# EVB-ANNA-B5_SCHEM_0007_mikroE.net
KiCad netlist of a schematic drawn in Altium Designer
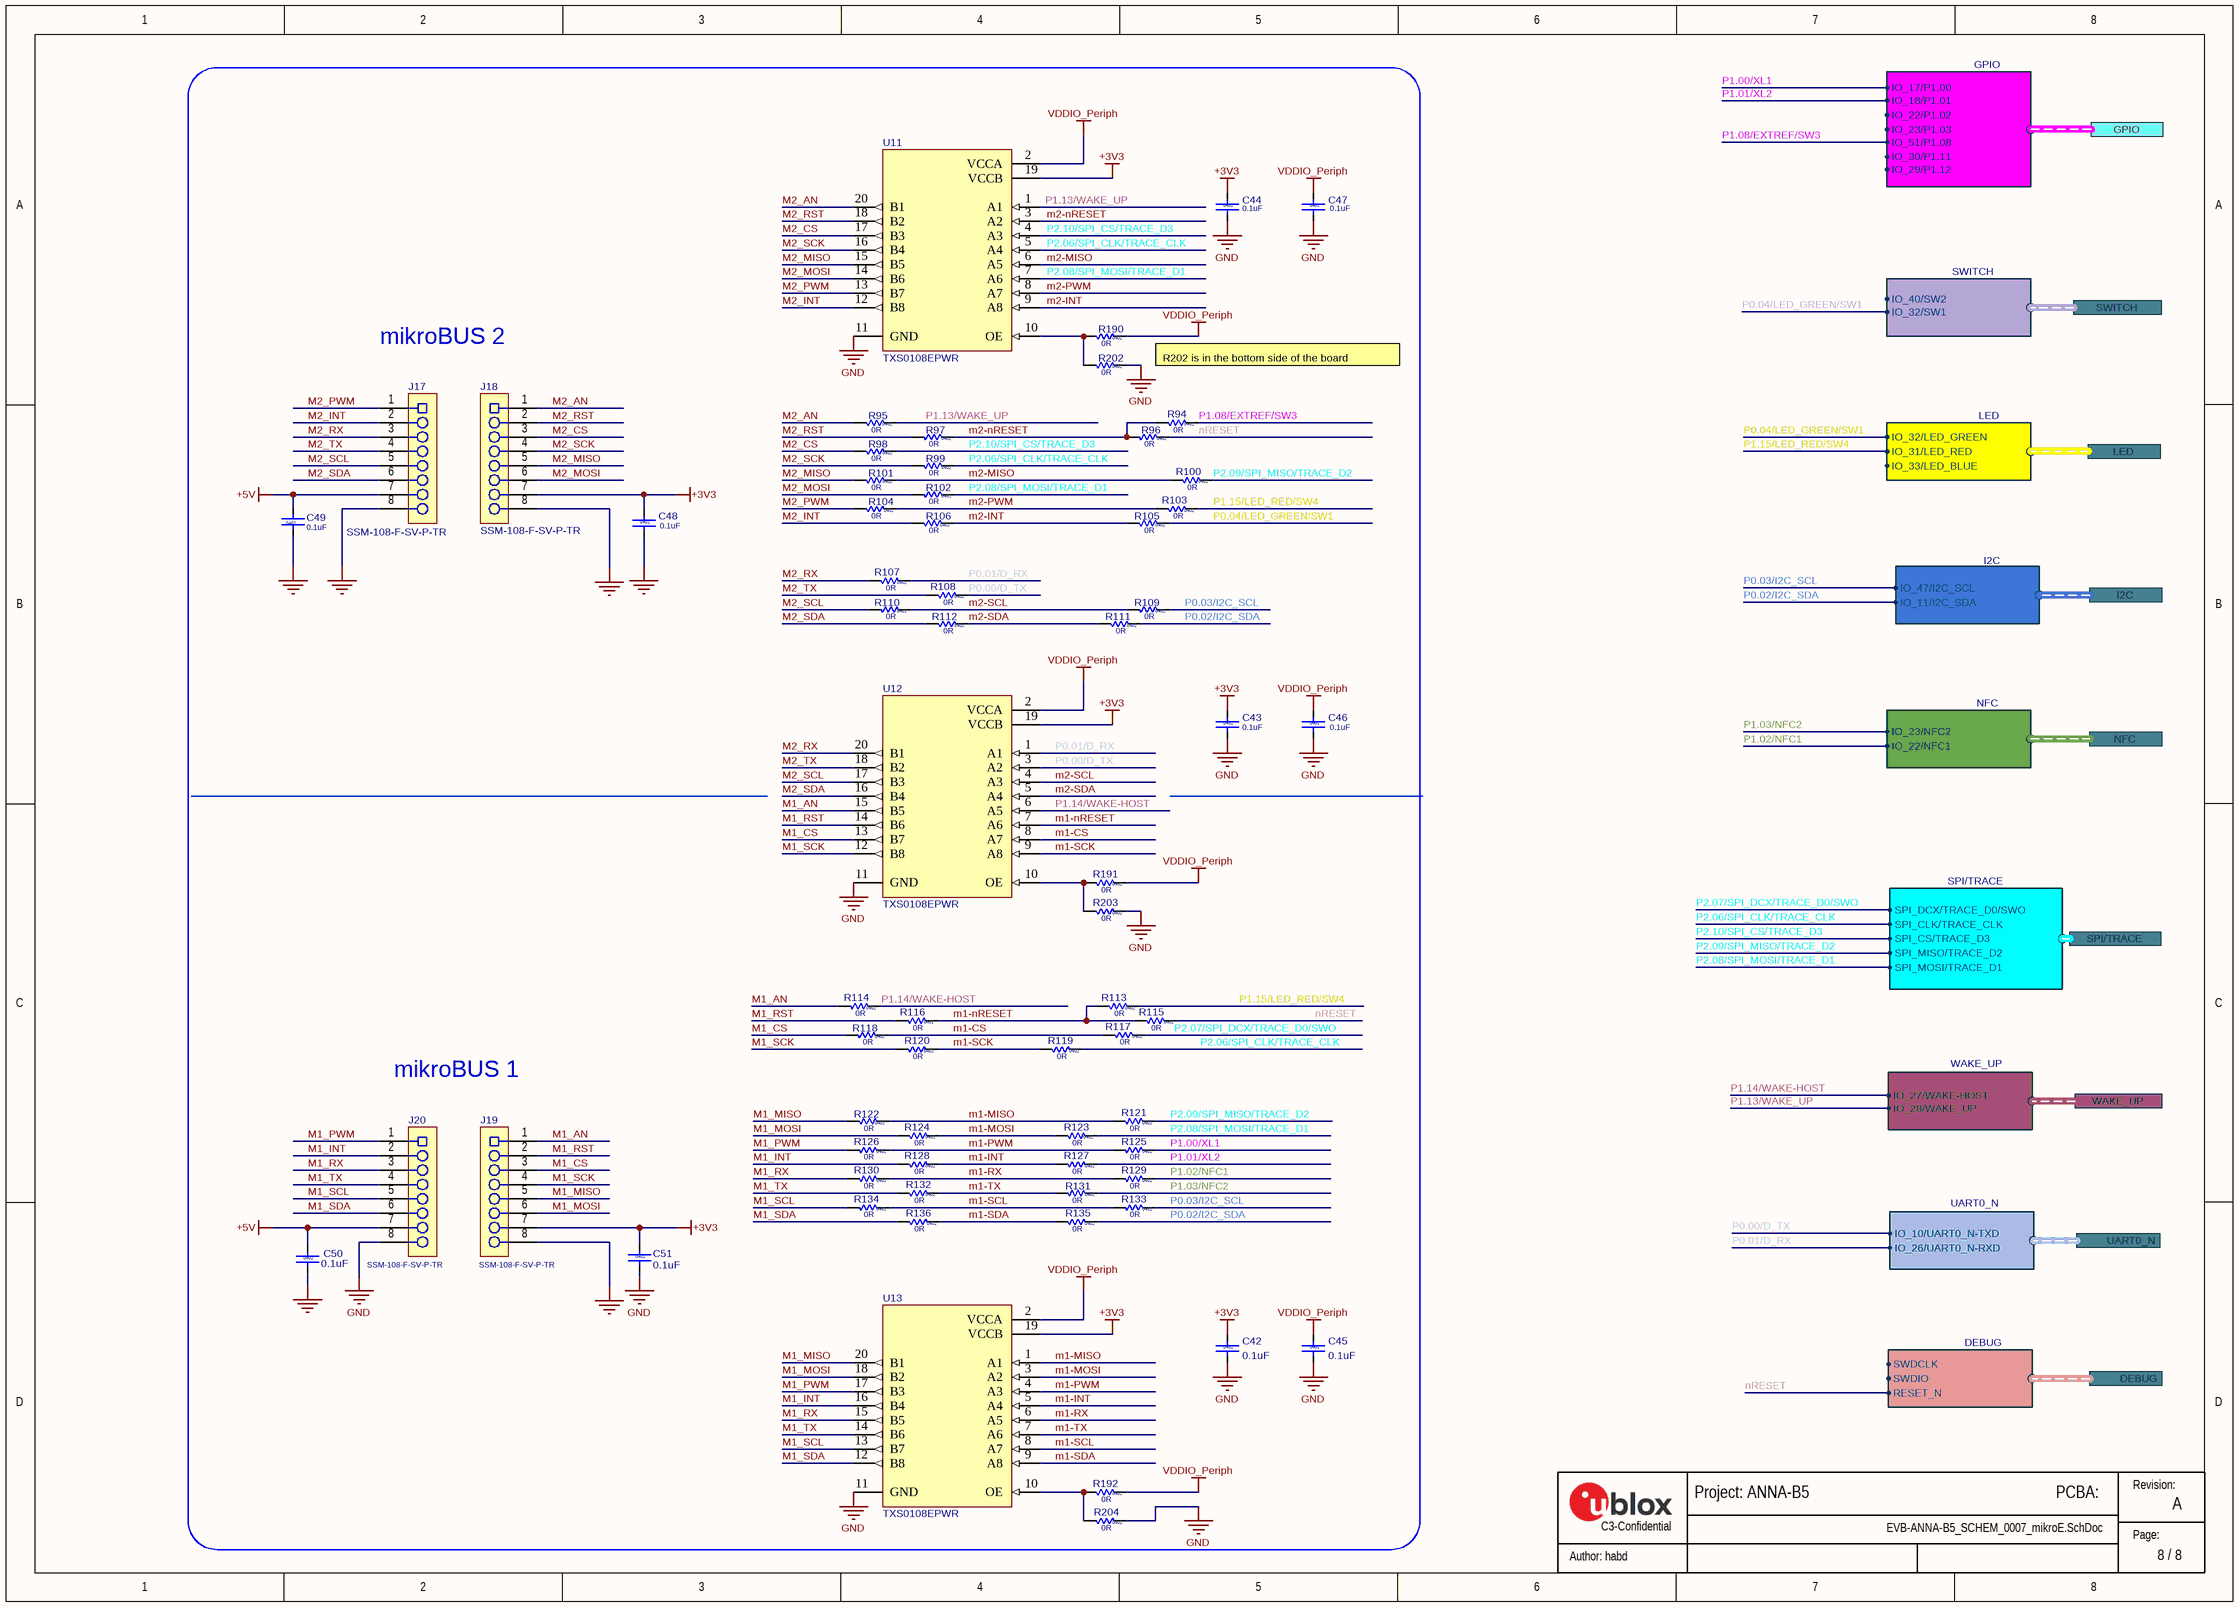
[diagram p0: EVB-ANNA-B5_SCHEM_0007_mikroE.SchDoc]

(export (version "E")
  (design (tool "Eeschema 10.0.6"))
  (components
    (comp (ref "C42")
      (value "0.1uF")
      (footprint "Cap 0402 HD")
      (description "Cap, Ceramic 0.1uF 10V 10% X5R 0402")
      (fields
        (field (name "SIZE") "0402")
        (field (name "PART NUMBER") "120-00016")
        (field (name "MANUFACTURER") "Murata Electronics North America")
      )
      (libsource (lib "Arena_Parts_DB_Lib") (part "Cap Chip"))
    )
    (comp (ref "C43")
      (value "0.1uF")
      (footprint "Cap 0402 HD")
      (description "Cap, Ceramic 0.1uF 10V 10% X5R 0402")
      (fields
        (field (name "SIZE") "0402")
        (field (name "PART NUMBER") "120-00016")
        (field (name "MANUFACTURER") "Murata Electronics North America")
      )
      (libsource (lib "Arena_Parts_DB_Lib") (part "Cap Chip"))
    )
    (comp (ref "C44")
      (value "0.1uF")
      (footprint "Cap 0402 HD")
      (description "Cap, Ceramic 0.1uF 10V 10% X5R 0402")
      (fields
        (field (name "SIZE") "0402")
        (field (name "PART NUMBER") "120-00016")
        (field (name "MANUFACTURER") "Murata Electronics North America")
      )
      (libsource (lib "Arena_Parts_DB_Lib") (part "Cap Chip"))
    )
    (comp (ref "C45")
      (value "0.1uF")
      (footprint "Cap 0402 HD")
      (description "Cap, Ceramic 0.1uF 10V 10% X5R 0402")
      (fields
        (field (name "SIZE") "0402")
        (field (name "PART NUMBER") "120-00016")
        (field (name "MANUFACTURER") "Murata Electronics North America")
      )
      (libsource (lib "Arena_Parts_DB_Lib") (part "Cap Chip"))
    )
    (comp (ref "C46")
      (value "0.1uF")
      (footprint "Cap 0402 HD")
      (description "Cap, Ceramic 0.1uF 10V 10% X5R 0402")
      (fields
        (field (name "SIZE") "0402")
        (field (name "PART NUMBER") "120-00016")
        (field (name "MANUFACTURER") "Murata Electronics North America")
      )
      (libsource (lib "Arena_Parts_DB_Lib") (part "Cap Chip"))
    )
    (comp (ref "C47")
      (value "0.1uF")
      (footprint "Cap 0402 HD")
      (description "Cap, Ceramic 0.1uF 10V 10% X5R 0402")
      (fields
        (field (name "SIZE") "0402")
        (field (name "PART NUMBER") "120-00016")
        (field (name "MANUFACTURER") "Murata Electronics North America")
      )
      (libsource (lib "Arena_Parts_DB_Lib") (part "Cap Chip"))
    )
    (comp (ref "C48")
      (value "0.1uF")
      (footprint "Cap 0402 HD")
      (description "Cap, Ceramic 0.1uF 10V 10% X5R 0402")
      (fields
        (field (name "SIZE") "0402")
        (field (name "PART NUMBER") "120-00016")
        (field (name "MANUFACTURER") "Murata Electronics North America")
      )
      (libsource (lib "Arena_Parts_DB_Lib") (part "Cap Chip"))
    )
    (comp (ref "C49")
      (value "0.1uF")
      (footprint "Cap 0402 HD")
      (description "Cap, Ceramic 0.1uF 10V 10% X5R 0402")
      (fields
        (field (name "SIZE") "0402")
        (field (name "PART NUMBER") "120-00016")
        (field (name "MANUFACTURER") "Murata Electronics North America")
      )
      (libsource (lib "Arena_Parts_DB_Lib") (part "Cap Chip"))
    )
    (comp (ref "C50")
      (value "0.1uF")
      (footprint "Cap 0402 HD")
      (description "Cap, Ceramic 0.1uF 10V 10% X5R 0402")
      (fields
        (field (name "SIZE") "0402")
        (field (name "PART NUMBER") "120-00016")
        (field (name "MANUFACTURER") "Murata Electronics North America")
      )
      (libsource (lib "Arena_Parts_DB_Lib") (part "Cap Chip"))
    )
    (comp (ref "C51")
      (value "0.1uF")
      (footprint "Cap 0402 HD")
      (description "Cap, Ceramic 0.1uF 10V 10% X5R 0402")
      (fields
        (field (name "SIZE") "0402")
        (field (name "PART NUMBER") "120-00016")
        (field (name "MANUFACTURER") "Murata Electronics North America")
      )
      (libsource (lib "Arena_Parts_DB_Lib") (part "Cap Chip"))
    )
    (comp (ref "J17")
      (value "130-00102")
      (footprint "SKT-0.1P-SSM-108-L-SV")
      (description "Socket Strip 0.1\" 8 Pin 1Row SMD Black")
      (fields
        (field (name "MANUFACTURER PART NUMBER 1") "SSM-108-F-SV-P-TR")
        (field (name "VOLTAGE") "572VDC")
      )
      (libsource (lib "") (part "CON-8Pin_1Row_1"))
    )
    (comp (ref "J18")
      (value "130-00102")
      (footprint "SKT-0.1P-SSM-108-L-SV")
      (description "Socket Strip 0.1\" 8 Pin 1Row SMD Black")
      (fields
        (field (name "MANUFACTURER PART NUMBER 1") "SSM-108-F-SV-P-TR")
        (field (name "VOLTAGE") "572VDC")
      )
      (libsource (lib "Arena_Parts_DB_Lib") (part "CON-8Pin_1Row"))
    )
    (comp (ref "J19")
      (value "130-00102")
      (footprint "SKT-0.1P-SSM-108-L-SV")
      (description "Socket Strip 0.1\" 8 Pin 1Row SMD Black")
      (fields
        (field (name "MANUFACTURER PART NUMBER 1") "SSM-108-F-SV-P-TR")
        (field (name "VOLTAGE") "572VDC")
      )
      (libsource (lib "Arena_Parts_DB_Lib") (part "CON-8Pin_1Row"))
    )
    (comp (ref "J20")
      (value "130-00102")
      (footprint "SKT-0.1P-SSM-108-L-SV")
      (description "Socket Strip 0.1\" 8 Pin 1Row SMD Black")
      (fields
        (field (name "MANUFACTURER PART NUMBER 1") "SSM-108-F-SV-P-TR")
        (field (name "VOLTAGE") "572VDC")
      )
      (libsource (lib "") (part "CON-8Pin_1Row_1"))
    )
    (comp (ref "R94")
      (value "0R")
      (footprint "RES 0402 HD")
      (description "RES THICK FILM CHIP 0402 0R 0 100mW")
      (fields
        (field (name "SIZE") "0402")
        (field (name "PART NUMBER") "UBXH18-0003002")
        (field (name "TOLERANCE") "0")
        (field (name "EDITOR") "charlotte.biber")
        (field (name "RELEASED BY") "peter.mueller")
      )
      (libsource (lib "UBX_Parts_DB_Lib") (part "Res sm"))
    )
    (comp (ref "R95")
      (value "0R")
      (footprint "RES 0402 HD")
      (description "RES THICK FILM CHIP 0402 0R 0 100mW")
      (fields
        (field (name "SIZE") "0402")
        (field (name "PART NUMBER") "UBXH18-0003002")
        (field (name "TOLERANCE") "0")
        (field (name "EDITOR") "charlotte.biber")
        (field (name "RELEASED BY") "peter.mueller")
      )
      (libsource (lib "UBX_Parts_DB_Lib") (part "Res sm"))
    )
    (comp (ref "R96")
      (value "0R")
      (footprint "RES 0402 HD")
      (description "RES THICK FILM CHIP 0402 0R 0 100mW")
      (fields
        (field (name "SIZE") "0402")
        (field (name "PART NUMBER") "UBXH18-0003002")
        (field (name "TOLERANCE") "0")
        (field (name "EDITOR") "charlotte.biber")
        (field (name "RELEASED BY") "peter.mueller")
      )
      (libsource (lib "UBX_Parts_DB_Lib") (part "Res sm"))
    )
    (comp (ref "R97")
      (value "0R")
      (footprint "RES 0402 HD")
      (description "RES THICK FILM CHIP 0402 0R 0 100mW")
      (fields
        (field (name "SIZE") "0402")
        (field (name "PART NUMBER") "UBXH18-0003002")
        (field (name "TOLERANCE") "0")
        (field (name "EDITOR") "charlotte.biber")
        (field (name "RELEASED BY") "peter.mueller")
      )
      (libsource (lib "UBX_Parts_DB_Lib") (part "Res sm"))
    )
    (comp (ref "R98")
      (value "0R")
      (footprint "RES 0402 HD")
      (description "RES THICK FILM CHIP 0402 0R 0 100mW")
      (fields
        (field (name "SIZE") "0402")
        (field (name "PART NUMBER") "UBXH18-0003002")
        (field (name "TOLERANCE") "0")
        (field (name "EDITOR") "charlotte.biber")
        (field (name "RELEASED BY") "peter.mueller")
      )
      (libsource (lib "UBX_Parts_DB_Lib") (part "Res sm"))
    )
    (comp (ref "R99")
      (value "0R")
      (footprint "RES 0402 HD")
      (description "RES THICK FILM CHIP 0402 0R 0 100mW")
      (fields
        (field (name "SIZE") "0402")
        (field (name "PART NUMBER") "UBXH18-0003002")
        (field (name "TOLERANCE") "0")
        (field (name "EDITOR") "charlotte.biber")
        (field (name "RELEASED BY") "peter.mueller")
      )
      (libsource (lib "UBX_Parts_DB_Lib") (part "Res sm"))
    )
    (comp (ref "R100")
      (value "0R")
      (footprint "RES 0402 HD")
      (description "RES THICK FILM CHIP 0402 0R 0 100mW")
      (fields
        (field (name "SIZE") "0402")
        (field (name "PART NUMBER") "UBXH18-0003002")
        (field (name "TOLERANCE") "0")
        (field (name "EDITOR") "charlotte.biber")
        (field (name "RELEASED BY") "peter.mueller")
      )
      (libsource (lib "UBX_Parts_DB_Lib") (part "Res sm"))
    )
    (comp (ref "R101")
      (value "0R")
      (footprint "RES 0402 HD")
      (description "RES THICK FILM CHIP 0402 0R 0 100mW")
      (fields
        (field (name "SIZE") "0402")
        (field (name "PART NUMBER") "UBXH18-0003002")
        (field (name "TOLERANCE") "0")
        (field (name "EDITOR") "charlotte.biber")
        (field (name "RELEASED BY") "peter.mueller")
      )
      (libsource (lib "UBX_Parts_DB_Lib") (part "Res sm"))
    )
    (comp (ref "R102")
      (value "0R")
      (footprint "RES 0402 HD")
      (description "RES THICK FILM CHIP 0402 0R 0 100mW")
      (fields
        (field (name "SIZE") "0402")
        (field (name "PART NUMBER") "UBXH18-0003002")
        (field (name "TOLERANCE") "0")
        (field (name "EDITOR") "charlotte.biber")
        (field (name "RELEASED BY") "peter.mueller")
      )
      (libsource (lib "UBX_Parts_DB_Lib") (part "Res sm"))
    )
    (comp (ref "R103")
      (value "0R")
      (footprint "RES 0402 HD")
      (description "RES THICK FILM CHIP 0402 0R 0 100mW")
      (fields
        (field (name "SIZE") "0402")
        (field (name "PART NUMBER") "UBXH18-0003002")
        (field (name "TOLERANCE") "0")
        (field (name "EDITOR") "charlotte.biber")
        (field (name "RELEASED BY") "peter.mueller")
      )
      (libsource (lib "UBX_Parts_DB_Lib") (part "Res sm"))
    )
    (comp (ref "R104")
      (value "0R")
      (footprint "RES 0402 HD")
      (description "RES THICK FILM CHIP 0402 0R 0 100mW")
      (fields
        (field (name "SIZE") "0402")
        (field (name "PART NUMBER") "UBXH18-0003002")
        (field (name "TOLERANCE") "0")
        (field (name "EDITOR") "charlotte.biber")
        (field (name "RELEASED BY") "peter.mueller")
      )
      (libsource (lib "UBX_Parts_DB_Lib") (part "Res sm"))
    )
    (comp (ref "R105")
      (value "0R")
      (footprint "RES 0402 HD")
      (description "RES THICK FILM CHIP 0402 0R 0 100mW")
      (fields
        (field (name "SIZE") "0402")
        (field (name "PART NUMBER") "UBXH18-0003002")
        (field (name "TOLERANCE") "0")
        (field (name "EDITOR") "charlotte.biber")
        (field (name "RELEASED BY") "peter.mueller")
      )
      (libsource (lib "UBX_Parts_DB_Lib") (part "Res sm"))
    )
    (comp (ref "R106")
      (value "0R")
      (footprint "RES 0402 HD")
      (description "RES THICK FILM CHIP 0402 0R 0 100mW")
      (fields
        (field (name "SIZE") "0402")
        (field (name "PART NUMBER") "UBXH18-0003002")
        (field (name "TOLERANCE") "0")
        (field (name "EDITOR") "charlotte.biber")
        (field (name "RELEASED BY") "peter.mueller")
      )
      (libsource (lib "UBX_Parts_DB_Lib") (part "Res sm"))
    )
    (comp (ref "R107")
      (value "0R")
      (footprint "RES 0402 HD")
      (description "RES THICK FILM CHIP 0402 0R 0 100mW")
      (fields
        (field (name "SIZE") "0402")
        (field (name "PART NUMBER") "UBXH18-0003002")
        (field (name "TOLERANCE") "0")
        (field (name "EDITOR") "charlotte.biber")
        (field (name "RELEASED BY") "peter.mueller")
      )
      (libsource (lib "UBX_Parts_DB_Lib") (part "Res sm"))
    )
    (comp (ref "R108")
      (value "0R")
      (footprint "RES 0402 HD")
      (description "RES THICK FILM CHIP 0402 0R 0 100mW")
      (fields
        (field (name "SIZE") "0402")
        (field (name "PART NUMBER") "UBXH18-0003002")
        (field (name "TOLERANCE") "0")
        (field (name "EDITOR") "charlotte.biber")
        (field (name "RELEASED BY") "peter.mueller")
      )
      (libsource (lib "UBX_Parts_DB_Lib") (part "Res sm"))
    )
    (comp (ref "R109")
      (value "0R")
      (footprint "RES 0402 HD")
      (description "RES THICK FILM CHIP 0402 0R 0 100mW")
      (fields
        (field (name "SIZE") "0402")
        (field (name "PART NUMBER") "UBXH18-0003002")
        (field (name "TOLERANCE") "0")
        (field (name "EDITOR") "charlotte.biber")
        (field (name "RELEASED BY") "peter.mueller")
      )
      (libsource (lib "UBX_Parts_DB_Lib") (part "Res sm"))
    )
    (comp (ref "R110")
      (value "0R")
      (footprint "RES 0402 HD")
      (description "RES THICK FILM CHIP 0402 0R 0 100mW")
      (fields
        (field (name "SIZE") "0402")
        (field (name "PART NUMBER") "UBXH18-0003002")
        (field (name "TOLERANCE") "0")
        (field (name "EDITOR") "charlotte.biber")
        (field (name "RELEASED BY") "peter.mueller")
      )
      (libsource (lib "UBX_Parts_DB_Lib") (part "Res sm"))
    )
    (comp (ref "R111")
      (value "0R")
      (footprint "RES 0402 HD")
      (description "RES THICK FILM CHIP 0402 0R 0 100mW")
      (fields
        (field (name "SIZE") "0402")
        (field (name "PART NUMBER") "UBXH18-0003002")
        (field (name "TOLERANCE") "0")
        (field (name "EDITOR") "charlotte.biber")
        (field (name "RELEASED BY") "peter.mueller")
      )
      (libsource (lib "UBX_Parts_DB_Lib") (part "Res sm"))
    )
    (comp (ref "R112")
      (value "0R")
      (footprint "RES 0402 HD")
      (description "RES THICK FILM CHIP 0402 0R 0 100mW")
      (fields
        (field (name "SIZE") "0402")
        (field (name "PART NUMBER") "UBXH18-0003002")
        (field (name "TOLERANCE") "0")
        (field (name "EDITOR") "charlotte.biber")
        (field (name "RELEASED BY") "peter.mueller")
      )
      (libsource (lib "UBX_Parts_DB_Lib") (part "Res sm"))
    )
    (comp (ref "R113")
      (value "0R")
      (footprint "RES 0402 HD")
      (description "RES THICK FILM CHIP 0402 0R 0 100mW")
      (fields
        (field (name "SIZE") "0402")
        (field (name "PART NUMBER") "UBXH18-0003002")
        (field (name "TOLERANCE") "0")
        (field (name "EDITOR") "charlotte.biber")
        (field (name "RELEASED BY") "peter.mueller")
      )
      (libsource (lib "UBX_Parts_DB_Lib") (part "Res sm"))
    )
    (comp (ref "R114")
      (value "0R")
      (footprint "RES 0402 HD")
      (description "RES THICK FILM CHIP 0402 0R 0 100mW")
      (fields
        (field (name "SIZE") "0402")
        (field (name "PART NUMBER") "UBXH18-0003002")
        (field (name "TOLERANCE") "0")
        (field (name "EDITOR") "charlotte.biber")
        (field (name "RELEASED BY") "peter.mueller")
      )
      (libsource (lib "UBX_Parts_DB_Lib") (part "Res sm"))
    )
    (comp (ref "R115")
      (value "0R")
      (footprint "RES 0402 HD")
      (description "RES THICK FILM CHIP 0402 0R 0 100mW")
      (fields
        (field (name "SIZE") "0402")
        (field (name "PART NUMBER") "UBXH18-0003002")
        (field (name "TOLERANCE") "0")
        (field (name "EDITOR") "charlotte.biber")
        (field (name "RELEASED BY") "peter.mueller")
      )
      (libsource (lib "UBX_Parts_DB_Lib") (part "Res sm"))
    )
    (comp (ref "R116")
      (value "0R")
      (footprint "RES 0402 HD")
      (description "RES THICK FILM CHIP 0402 0R 0 100mW")
      (fields
        (field (name "SIZE") "0402")
        (field (name "PART NUMBER") "UBXH18-0003002")
        (field (name "TOLERANCE") "0")
        (field (name "EDITOR") "charlotte.biber")
        (field (name "RELEASED BY") "peter.mueller")
      )
      (libsource (lib "UBX_Parts_DB_Lib") (part "Res sm"))
    )
    (comp (ref "R117")
      (value "0R")
      (footprint "RES 0402 HD")
      (description "RES THICK FILM CHIP 0402 0R 0 100mW")
      (fields
        (field (name "SIZE") "0402")
        (field (name "PART NUMBER") "UBXH18-0003002")
        (field (name "TOLERANCE") "0")
        (field (name "EDITOR") "charlotte.biber")
        (field (name "RELEASED BY") "peter.mueller")
      )
      (libsource (lib "UBX_Parts_DB_Lib") (part "Res sm"))
    )
    (comp (ref "R118")
      (value "0R")
      (footprint "RES 0402 HD")
      (description "RES THICK FILM CHIP 0402 0R 0 100mW")
      (fields
        (field (name "SIZE") "0402")
        (field (name "PART NUMBER") "UBXH18-0003002")
        (field (name "TOLERANCE") "0")
        (field (name "EDITOR") "charlotte.biber")
        (field (name "RELEASED BY") "peter.mueller")
      )
      (libsource (lib "UBX_Parts_DB_Lib") (part "Res sm"))
    )
    (comp (ref "R119")
      (value "0R")
      (footprint "RES 0402 HD")
      (description "RES THICK FILM CHIP 0402 0R 0 100mW")
      (fields
        (field (name "SIZE") "0402")
        (field (name "PART NUMBER") "UBXH18-0003002")
        (field (name "TOLERANCE") "0")
        (field (name "EDITOR") "charlotte.biber")
        (field (name "RELEASED BY") "peter.mueller")
      )
      (libsource (lib "UBX_Parts_DB_Lib") (part "Res sm"))
    )
    (comp (ref "R120")
      (value "0R")
      (footprint "RES 0402 HD")
      (description "RES THICK FILM CHIP 0402 0R 0 100mW")
      (fields
        (field (name "SIZE") "0402")
        (field (name "PART NUMBER") "UBXH18-0003002")
        (field (name "TOLERANCE") "0")
        (field (name "EDITOR") "charlotte.biber")
        (field (name "RELEASED BY") "peter.mueller")
      )
      (libsource (lib "UBX_Parts_DB_Lib") (part "Res sm"))
    )
    (comp (ref "R121")
      (value "0R")
      (footprint "RES 0402 HD")
      (description "RES THICK FILM CHIP 0402 0R 0 100mW")
      (fields
        (field (name "SIZE") "0402")
        (field (name "PART NUMBER") "UBXH18-0003002")
        (field (name "TOLERANCE") "0")
        (field (name "EDITOR") "charlotte.biber")
        (field (name "RELEASED BY") "peter.mueller")
      )
      (libsource (lib "UBX_Parts_DB_Lib") (part "Res sm"))
    )
    (comp (ref "R122")
      (value "0R")
      (footprint "RES 0402 HD")
      (description "RES THICK FILM CHIP 0402 0R 0 100mW")
      (fields
        (field (name "SIZE") "0402")
        (field (name "PART NUMBER") "UBXH18-0003002")
        (field (name "TOLERANCE") "0")
        (field (name "EDITOR") "charlotte.biber")
        (field (name "RELEASED BY") "peter.mueller")
      )
      (libsource (lib "UBX_Parts_DB_Lib") (part "Res sm"))
    )
    (comp (ref "R123")
      (value "0R")
      (footprint "RES 0402 HD")
      (description "RES THICK FILM CHIP 0402 0R 0 100mW")
      (fields
        (field (name "SIZE") "0402")
        (field (name "PART NUMBER") "UBXH18-0003002")
        (field (name "TOLERANCE") "0")
        (field (name "EDITOR") "charlotte.biber")
        (field (name "RELEASED BY") "peter.mueller")
      )
      (libsource (lib "UBX_Parts_DB_Lib") (part "Res sm"))
    )
    (comp (ref "R124")
      (value "0R")
      (footprint "RES 0402 HD")
      (description "RES THICK FILM CHIP 0402 0R 0 100mW")
      (fields
        (field (name "SIZE") "0402")
        (field (name "PART NUMBER") "UBXH18-0003002")
        (field (name "TOLERANCE") "0")
        (field (name "EDITOR") "charlotte.biber")
        (field (name "RELEASED BY") "peter.mueller")
      )
      (libsource (lib "UBX_Parts_DB_Lib") (part "Res sm"))
    )
    (comp (ref "R125")
      (value "0R")
      (footprint "RES 0402 HD")
      (description "RES THICK FILM CHIP 0402 0R 0 100mW")
      (fields
        (field (name "SIZE") "0402")
        (field (name "PART NUMBER") "UBXH18-0003002")
        (field (name "TOLERANCE") "0")
        (field (name "EDITOR") "charlotte.biber")
        (field (name "RELEASED BY") "peter.mueller")
      )
      (libsource (lib "UBX_Parts_DB_Lib") (part "Res sm"))
    )
    (comp (ref "R126")
      (value "0R")
      (footprint "RES 0402 HD")
      (description "RES THICK FILM CHIP 0402 0R 0 100mW")
      (fields
        (field (name "SIZE") "0402")
        (field (name "PART NUMBER") "UBXH18-0003002")
        (field (name "TOLERANCE") "0")
        (field (name "EDITOR") "charlotte.biber")
        (field (name "RELEASED BY") "peter.mueller")
      )
      (libsource (lib "UBX_Parts_DB_Lib") (part "Res sm"))
    )
    (comp (ref "R127")
      (value "0R")
      (footprint "RES 0402 HD")
      (description "RES THICK FILM CHIP 0402 0R 0 100mW")
      (fields
        (field (name "SIZE") "0402")
        (field (name "PART NUMBER") "UBXH18-0003002")
        (field (name "TOLERANCE") "0")
        (field (name "EDITOR") "charlotte.biber")
        (field (name "RELEASED BY") "peter.mueller")
      )
      (libsource (lib "UBX_Parts_DB_Lib") (part "Res sm"))
    )
    (comp (ref "R128")
      (value "0R")
      (footprint "RES 0402 HD")
      (description "RES THICK FILM CHIP 0402 0R 0 100mW")
      (fields
        (field (name "SIZE") "0402")
        (field (name "PART NUMBER") "UBXH18-0003002")
        (field (name "TOLERANCE") "0")
        (field (name "EDITOR") "charlotte.biber")
        (field (name "RELEASED BY") "peter.mueller")
      )
      (libsource (lib "UBX_Parts_DB_Lib") (part "Res sm"))
    )
    (comp (ref "R129")
      (value "0R")
      (footprint "RES 0402 HD")
      (description "RES THICK FILM CHIP 0402 0R 0 100mW")
      (fields
        (field (name "SIZE") "0402")
        (field (name "PART NUMBER") "UBXH18-0003002")
        (field (name "TOLERANCE") "0")
        (field (name "EDITOR") "charlotte.biber")
        (field (name "RELEASED BY") "peter.mueller")
      )
      (libsource (lib "UBX_Parts_DB_Lib") (part "Res sm"))
    )
    (comp (ref "R130")
      (value "0R")
      (footprint "RES 0402 HD")
      (description "RES THICK FILM CHIP 0402 0R 0 100mW")
      (fields
        (field (name "SIZE") "0402")
        (field (name "PART NUMBER") "UBXH18-0003002")
        (field (name "TOLERANCE") "0")
        (field (name "EDITOR") "charlotte.biber")
        (field (name "RELEASED BY") "peter.mueller")
      )
      (libsource (lib "UBX_Parts_DB_Lib") (part "Res sm"))
    )
    (comp (ref "R131")
      (value "0R")
      (footprint "RES 0402 HD")
      (description "RES THICK FILM CHIP 0402 0R 0 100mW")
      (fields
        (field (name "SIZE") "0402")
        (field (name "PART NUMBER") "UBXH18-0003002")
        (field (name "TOLERANCE") "0")
        (field (name "EDITOR") "charlotte.biber")
        (field (name "RELEASED BY") "peter.mueller")
      )
      (libsource (lib "UBX_Parts_DB_Lib") (part "Res sm"))
    )
    (comp (ref "R132")
      (value "0R")
      (footprint "RES 0402 HD")
      (description "RES THICK FILM CHIP 0402 0R 0 100mW")
      (fields
        (field (name "SIZE") "0402")
        (field (name "PART NUMBER") "UBXH18-0003002")
        (field (name "TOLERANCE") "0")
        (field (name "EDITOR") "charlotte.biber")
        (field (name "RELEASED BY") "peter.mueller")
      )
      (libsource (lib "UBX_Parts_DB_Lib") (part "Res sm"))
    )
    (comp (ref "R133")
      (value "0R")
      (footprint "RES 0402 HD")
      (description "RES THICK FILM CHIP 0402 0R 0 100mW")
      (fields
        (field (name "SIZE") "0402")
        (field (name "PART NUMBER") "UBXH18-0003002")
        (field (name "TOLERANCE") "0")
        (field (name "EDITOR") "charlotte.biber")
        (field (name "RELEASED BY") "peter.mueller")
      )
      (libsource (lib "UBX_Parts_DB_Lib") (part "Res sm"))
    )
    (comp (ref "R134")
      (value "0R")
      (footprint "RES 0402 HD")
      (description "RES THICK FILM CHIP 0402 0R 0 100mW")
      (fields
        (field (name "SIZE") "0402")
        (field (name "PART NUMBER") "UBXH18-0003002")
        (field (name "TOLERANCE") "0")
        (field (name "EDITOR") "charlotte.biber")
        (field (name "RELEASED BY") "peter.mueller")
      )
      (libsource (lib "UBX_Parts_DB_Lib") (part "Res sm"))
    )
    (comp (ref "R135")
      (value "0R")
      (footprint "RES 0402 HD")
      (description "RES THICK FILM CHIP 0402 0R 0 100mW")
      (fields
        (field (name "SIZE") "0402")
        (field (name "PART NUMBER") "UBXH18-0003002")
        (field (name "TOLERANCE") "0")
        (field (name "EDITOR") "charlotte.biber")
        (field (name "RELEASED BY") "peter.mueller")
      )
      (libsource (lib "UBX_Parts_DB_Lib") (part "Res sm"))
    )
    (comp (ref "R136")
      (value "0R")
      (footprint "RES 0402 HD")
      (description "RES THICK FILM CHIP 0402 0R 0 100mW")
      (fields
        (field (name "SIZE") "0402")
        (field (name "PART NUMBER") "UBXH18-0003002")
        (field (name "TOLERANCE") "0")
        (field (name "EDITOR") "charlotte.biber")
        (field (name "RELEASED BY") "peter.mueller")
      )
      (libsource (lib "UBX_Parts_DB_Lib") (part "Res sm"))
    )
    (comp (ref "R190")
      (value "0R")
      (footprint "RES 0402 HD")
      (description "RES THICK FILM CHIP 0402 0R 0 100mW")
      (fields
        (field (name "SIZE") "0402")
        (field (name "PART NUMBER") "UBXH18-0003002")
        (field (name "TOLERANCE") "0")
        (field (name "EDITOR") "charlotte.biber")
        (field (name "RELEASED BY") "peter.mueller")
      )
      (libsource (lib "UBX_Parts_DB_Lib") (part "Res sm"))
    )
    (comp (ref "R191")
      (value "0R")
      (footprint "RES 0402 HD")
      (description "RES THICK FILM CHIP 0402 0R 0 100mW")
      (fields
        (field (name "SIZE") "0402")
        (field (name "PART NUMBER") "UBXH18-0003002")
        (field (name "TOLERANCE") "0")
        (field (name "EDITOR") "charlotte.biber")
        (field (name "RELEASED BY") "peter.mueller")
      )
      (libsource (lib "UBX_Parts_DB_Lib") (part "Res sm"))
    )
    (comp (ref "R192")
      (value "0R")
      (footprint "RES 0402 HD")
      (description "RES THICK FILM CHIP 0402 0R 0 100mW")
      (fields
        (field (name "SIZE") "0402")
        (field (name "PART NUMBER") "UBXH18-0003002")
        (field (name "TOLERANCE") "0")
        (field (name "EDITOR") "charlotte.biber")
        (field (name "RELEASED BY") "peter.mueller")
      )
      (libsource (lib "UBX_Parts_DB_Lib") (part "Res sm"))
    )
    (comp (ref "R202")
      (value "0R")
      (footprint "RES 0402 HD")
      (description "RES THICK FILM CHIP 0402 0R 0 100mW")
      (fields
        (field (name "SIZE") "0402")
        (field (name "PART NUMBER") "UBXH18-0003002")
        (field (name "TOLERANCE") "0")
        (field (name "EDITOR") "charlotte.biber")
        (field (name "RELEASED BY") "peter.mueller")
      )
      (libsource (lib "UBX_Parts_DB_Lib") (part "Res sm"))
    )
    (comp (ref "R203")
      (value "0R")
      (footprint "RES 0402 HD")
      (description "RES THICK FILM CHIP 0402 0R 0 100mW")
      (fields
        (field (name "SIZE") "0402")
        (field (name "PART NUMBER") "UBXH18-0003002")
        (field (name "TOLERANCE") "0")
        (field (name "EDITOR") "charlotte.biber")
        (field (name "RELEASED BY") "peter.mueller")
      )
      (libsource (lib "UBX_Parts_DB_Lib") (part "Res sm"))
    )
    (comp (ref "R204")
      (value "0R")
      (footprint "RES 0402 HD")
      (description "RES THICK FILM CHIP 0402 0R 0 100mW")
      (fields
        (field (name "SIZE") "0402")
        (field (name "PART NUMBER") "UBXH18-0003002")
        (field (name "TOLERANCE") "0")
        (field (name "EDITOR") "charlotte.biber")
        (field (name "RELEASED BY") "peter.mueller")
      )
      (libsource (lib "UBX_Parts_DB_Lib") (part "Res sm"))
    )
    (comp (ref "U11")
      (value "UBXH10-0000036")
      (footprint "TSOP0.65P6.40X1.20-20Pin")
      (description "TXS0108 8-BIT BIDIRECTIONAL VOLTAGE-LEVEL TRANSLATOR")
      (fields
        (field (name "MANUFACTURER P/N") "TXS0108EPWR")
        (field (name "MANUFACTURER") "Texas Instruments")
        (field (name "EDITOR") "roland.rust")
        (field (name "RELEASED BY") "adam.johansson")
      )
      (libsource (lib "UBX_Parts_DB_Lib") (part "TXS0108EPWR"))
    )
    (comp (ref "U12")
      (value "UBXH10-0000036")
      (footprint "TSOP0.65P6.40X1.20-20Pin")
      (description "TXS0108 8-BIT BIDIRECTIONAL VOLTAGE-LEVEL TRANSLATOR")
      (fields
        (field (name "MANUFACTURER P/N") "TXS0108EPWR")
        (field (name "MANUFACTURER") "Texas Instruments")
        (field (name "EDITOR") "roland.rust")
        (field (name "RELEASED BY") "adam.johansson")
      )
      (libsource (lib "UBX_Parts_DB_Lib") (part "TXS0108EPWR"))
    )
    (comp (ref "U13")
      (value "UBXH10-0000036")
      (footprint "TSOP0.65P6.40X1.20-20Pin")
      (description "TXS0108 8-BIT BIDIRECTIONAL VOLTAGE-LEVEL TRANSLATOR")
      (fields
        (field (name "MANUFACTURER P/N") "TXS0108EPWR")
        (field (name "MANUFACTURER") "Texas Instruments")
        (field (name "EDITOR") "roland.rust")
        (field (name "RELEASED BY") "adam.johansson")
      )
      (libsource (lib "UBX_Parts_DB_Lib") (part "TXS0108EPWR"))
    )
  )
  (nets
    (net (code "10") (name "+3V3") (class "Default")
      (node (ref "C42") (pin "1") (pinfunction "1_1") (pintype "passive"))
      (node (ref "C43") (pin "1") (pinfunction "1_1") (pintype "passive"))
      (node (ref "C44") (pin "1") (pinfunction "1_1") (pintype "passive"))
      (node (ref "C48") (pin "1") (pinfunction "1_1") (pintype "passive"))
      (node (ref "C51") (pin "1") (pinfunction "1_1") (pintype "passive"))
      (node (ref "J18") (pin "7") (pintype "passive"))
      (node (ref "J19") (pin "7") (pintype "passive"))
      (node (ref "U11") (pin "19") (pinfunction "VCCB_19") (pintype "power_in"))
      (node (ref "U12") (pin "19") (pinfunction "VCCB_19") (pintype "power_in"))
      (node (ref "U13") (pin "19") (pinfunction "VCCB_19") (pintype "power_in"))
    )
    (net (code "11") (name "+5V") (class "Default")
      (node (ref "C49") (pin "2") (pinfunction "2_2") (pintype "passive"))
      (node (ref "C50") (pin "1") (pinfunction "1_1") (pintype "passive"))
      (node (ref "J17") (pin "7") (pintype "passive"))
      (node (ref "J20") (pin "7") (pintype "passive"))
    )
    (net (code "12") (name "/M1_AN") (class "Default")
      (node (ref "J19") (pin "1") (pintype "passive"))
      (node (ref "R114") (pin "1") (pinfunction "1_1") (pintype "passive"))
      (node (ref "U12") (pin "15") (pinfunction "B5_15") (pintype "output"))
    )
    (net (code "13") (name "/M1_CS") (class "Default")
      (node (ref "J19") (pin "3") (pintype "passive"))
      (node (ref "R118") (pin "1") (pinfunction "1_1") (pintype "passive"))
      (node (ref "U12") (pin "13") (pinfunction "B7_13") (pintype "output"))
    )
    (net (code "14") (name "/M1_INT") (class "Default")
      (node (ref "J20") (pin "2") (pintype "passive"))
      (node (ref "R128") (pin "1") (pinfunction "1_1") (pintype "passive"))
      (node (ref "U13") (pin "16") (pinfunction "B4_16") (pintype "output"))
    )
    (net (code "15") (name "/M1_MISO") (class "Default")
      (node (ref "J19") (pin "5") (pintype "passive"))
      (node (ref "R122") (pin "1") (pinfunction "1_1") (pintype "passive"))
      (node (ref "U13") (pin "20") (pinfunction "B1_20") (pintype "output"))
    )
    (net (code "16") (name "/M1_MOSI") (class "Default")
      (node (ref "J19") (pin "6") (pintype "passive"))
      (node (ref "R124") (pin "1") (pinfunction "1_1") (pintype "passive"))
      (node (ref "U13") (pin "18") (pinfunction "B2_18") (pintype "output"))
    )
    (net (code "17") (name "/M1_PWM") (class "Default")
      (node (ref "J20") (pin "1") (pintype "passive"))
      (node (ref "R126") (pin "1") (pinfunction "1_1") (pintype "passive"))
      (node (ref "U13") (pin "17") (pinfunction "B3_17") (pintype "output"))
    )
    (net (code "18") (name "/M1_RST") (class "Default")
      (node (ref "J19") (pin "2") (pintype "passive"))
      (node (ref "R116") (pin "1") (pinfunction "1_1") (pintype "passive"))
      (node (ref "U12") (pin "14") (pinfunction "B6_14") (pintype "output"))
    )
    (net (code "19") (name "/M1_RX") (class "Default")
      (node (ref "J20") (pin "3") (pintype "passive"))
      (node (ref "R130") (pin "1") (pinfunction "1_1") (pintype "passive"))
      (node (ref "U13") (pin "15") (pinfunction "B5_15") (pintype "output"))
    )
    (net (code "20") (name "/M1_SCK") (class "Default")
      (node (ref "J19") (pin "4") (pintype "passive"))
      (node (ref "R120") (pin "1") (pinfunction "1_1") (pintype "passive"))
      (node (ref "U12") (pin "12") (pinfunction "B8_12") (pintype "output"))
    )
    (net (code "21") (name "/M1_SCL") (class "Default")
      (node (ref "J20") (pin "5") (pintype "passive"))
      (node (ref "R134") (pin "1") (pinfunction "1_1") (pintype "passive"))
      (node (ref "U13") (pin "13") (pinfunction "B7_13") (pintype "output"))
    )
    (net (code "22") (name "/M1_SDA") (class "Default")
      (node (ref "J20") (pin "6") (pintype "passive"))
      (node (ref "R136") (pin "1") (pinfunction "1_1") (pintype "passive"))
      (node (ref "U13") (pin "12") (pinfunction "B8_12") (pintype "output"))
    )
    (net (code "23") (name "/M1_TX") (class "Default")
      (node (ref "J20") (pin "4") (pintype "passive"))
      (node (ref "R132") (pin "1") (pinfunction "1_1") (pintype "passive"))
      (node (ref "U13") (pin "14") (pinfunction "B6_14") (pintype "output"))
    )
    (net (code "24") (name "/M2_AN") (class "Default")
      (node (ref "J18") (pin "1") (pintype "passive"))
      (node (ref "R95") (pin "1") (pinfunction "1_1") (pintype "passive"))
      (node (ref "U11") (pin "20") (pinfunction "B1_20") (pintype "output"))
    )
    (net (code "25") (name "/M2_CS") (class "Default")
      (node (ref "J18") (pin "3") (pintype "passive"))
      (node (ref "R98") (pin "1") (pinfunction "1_1") (pintype "passive"))
      (node (ref "U11") (pin "17") (pinfunction "B3_17") (pintype "output"))
    )
    (net (code "26") (name "/M2_INT") (class "Default")
      (node (ref "J17") (pin "2") (pintype "passive"))
      (node (ref "R106") (pin "1") (pinfunction "1_1") (pintype "passive"))
      (node (ref "U11") (pin "12") (pinfunction "B8_12") (pintype "output"))
    )
    (net (code "27") (name "/M2_MISO") (class "Default")
      (node (ref "J18") (pin "5") (pintype "passive"))
      (node (ref "R101") (pin "1") (pinfunction "1_1") (pintype "passive"))
      (node (ref "U11") (pin "15") (pinfunction "B5_15") (pintype "output"))
    )
    (net (code "28") (name "/M2_MOSI") (class "Default")
      (node (ref "J18") (pin "6") (pintype "passive"))
      (node (ref "R102") (pin "1") (pinfunction "1_1") (pintype "passive"))
      (node (ref "U11") (pin "14") (pinfunction "B6_14") (pintype "output"))
    )
    (net (code "29") (name "/M2_PWM") (class "Default")
      (node (ref "J17") (pin "1") (pintype "passive"))
      (node (ref "R104") (pin "1") (pinfunction "1_1") (pintype "passive"))
      (node (ref "U11") (pin "13") (pinfunction "B7_13") (pintype "output"))
    )
    (net (code "30") (name "/M2_RST") (class "Default")
      (node (ref "J18") (pin "2") (pintype "passive"))
      (node (ref "R97") (pin "1") (pinfunction "1_1") (pintype "passive"))
      (node (ref "U11") (pin "18") (pinfunction "B2_18") (pintype "output"))
    )
    (net (code "31") (name "/M2_RX") (class "Default")
      (node (ref "J17") (pin "3") (pintype "passive"))
      (node (ref "R107") (pin "1") (pinfunction "1_1") (pintype "passive"))
      (node (ref "U12") (pin "20") (pinfunction "B1_20") (pintype "output"))
    )
    (net (code "32") (name "/M2_SCK") (class "Default")
      (node (ref "J18") (pin "4") (pintype "passive"))
      (node (ref "R99") (pin "1") (pinfunction "1_1") (pintype "passive"))
      (node (ref "U11") (pin "16") (pinfunction "B4_16") (pintype "output"))
    )
    (net (code "33") (name "/M2_SCL") (class "Default")
      (node (ref "J17") (pin "5") (pintype "passive"))
      (node (ref "R110") (pin "1") (pinfunction "1_1") (pintype "passive"))
      (node (ref "U12") (pin "17") (pinfunction "B3_17") (pintype "output"))
    )
    (net (code "34") (name "/M2_SDA") (class "Default")
      (node (ref "J17") (pin "6") (pintype "passive"))
      (node (ref "R112") (pin "1") (pinfunction "1_1") (pintype "passive"))
      (node (ref "U12") (pin "16") (pinfunction "B4_16") (pintype "output"))
    )
    (net (code "35") (name "/M2_TX") (class "Default")
      (node (ref "J17") (pin "4") (pintype "passive"))
      (node (ref "R108") (pin "1") (pinfunction "1_1") (pintype "passive"))
      (node (ref "U12") (pin "18") (pinfunction "B2_18") (pintype "output"))
    )
    (net (code "36") (name "/P0.00{slash}D_TX") (class "Default")
      (node (ref "R108") (pin "2") (pinfunction "2_2") (pintype "passive"))
      (node (ref "U12") (pin "3") (pinfunction "A2_3") (pintype "input"))
    )
    (net (code "37") (name "/P0.01{slash}D_RX") (class "Default")
      (node (ref "R107") (pin "2") (pinfunction "2_2") (pintype "passive"))
      (node (ref "U12") (pin "1") (pinfunction "A1_1") (pintype "input"))
    )
    (net (code "38") (name "/P0.02{slash}I2C_SDA") (class "Default")
      (node (ref "R111") (pin "2") (pinfunction "2_2") (pintype "passive"))
      (node (ref "R135") (pin "2") (pinfunction "2_2") (pintype "passive"))
    )
    (net (code "39") (name "/P0.03{slash}I2C_SCL") (class "Default")
      (node (ref "R109") (pin "2") (pinfunction "2_2") (pintype "passive"))
      (node (ref "R133") (pin "2") (pinfunction "2_2") (pintype "passive"))
    )
    (net (code "40") (name "/P0.04{slash}LED_GREEN{slash}SW1") (class "Default")
      (node (ref "R105") (pin "2") (pinfunction "2_2") (pintype "passive"))
    )
    (net (code "41") (name "/P1.00{slash}XL1") (class "Default")
      (node (ref "R125") (pin "2") (pinfunction "2_2") (pintype "passive"))
    )
    (net (code "42") (name "/P1.01{slash}XL2") (class "Default")
      (node (ref "R127") (pin "2") (pinfunction "2_2") (pintype "passive"))
    )
    (net (code "43") (name "/P1.02{slash}NFC1") (class "Default")
      (node (ref "R129") (pin "2") (pinfunction "2_2") (pintype "passive"))
    )
    (net (code "44") (name "/P1.03{slash}NFC2") (class "Default")
      (node (ref "R131") (pin "2") (pinfunction "2_2") (pintype "passive"))
    )
    (net (code "45") (name "/P1.08{slash}EXTREF{slash}SW3") (class "Default")
      (node (ref "R94") (pin "2") (pinfunction "2_2") (pintype "passive"))
    )
    (net (code "46") (name "/P1.13{slash}WAKE_UP") (class "Default")
      (node (ref "R95") (pin "2") (pinfunction "2_2") (pintype "passive"))
      (node (ref "U11") (pin "1") (pinfunction "A1_1") (pintype "input"))
    )
    (net (code "47") (name "/P1.14{slash}WAKE-HOST") (class "Default")
      (node (ref "R114") (pin "2") (pinfunction "2_2") (pintype "passive"))
      (node (ref "U12") (pin "6") (pinfunction "A5_6") (pintype "input"))
    )
    (net (code "48") (name "/P1.15{slash}LED_RED{slash}SW4") (class "Default")
      (node (ref "R103") (pin "2") (pinfunction "2_2") (pintype "passive"))
      (node (ref "R113") (pin "2") (pinfunction "2_2") (pintype "passive"))
    )
    (net (code "49") (name "/P2.06{slash}SPI_CLK{slash}TRACE_CLK") (class "Default")
      (node (ref "R119") (pin "2") (pinfunction "2_2") (pintype "passive"))
      (node (ref "R99") (pin "2") (pinfunction "2_2") (pintype "passive"))
      (node (ref "U11") (pin "5") (pinfunction "A4_5") (pintype "input"))
    )
    (net (code "50") (name "/P2.07{slash}SPI_DCX{slash}TRACE_D0{slash}SWO") (class "Default")
      (node (ref "R117") (pin "2") (pinfunction "2_2") (pintype "passive"))
    )
    (net (code "51") (name "/P2.08{slash}SPI_MOSI{slash}TRACE_D1") (class "Default")
      (node (ref "R102") (pin "2") (pinfunction "2_2") (pintype "passive"))
      (node (ref "R123") (pin "2") (pinfunction "2_2") (pintype "passive"))
      (node (ref "U11") (pin "7") (pinfunction "A6_7") (pintype "input"))
    )
    (net (code "52") (name "/P2.09{slash}SPI_MISO{slash}TRACE_D2") (class "Default")
      (node (ref "R100") (pin "2") (pinfunction "2_2") (pintype "passive"))
      (node (ref "R121") (pin "2") (pinfunction "2_2") (pintype "passive"))
    )
    (net (code "53") (name "/P2.10{slash}SPI_CS{slash}TRACE_D3") (class "Default")
      (node (ref "R98") (pin "2") (pinfunction "2_2") (pintype "passive"))
      (node (ref "U11") (pin "4") (pinfunction "A3_4") (pintype "input"))
    )
    (net (code "54") (name "/m1-CS") (class "Default")
      (node (ref "R117") (pin "1") (pinfunction "1_1") (pintype "passive"))
      (node (ref "R118") (pin "2") (pinfunction "2_2") (pintype "passive"))
      (node (ref "U12") (pin "8") (pinfunction "A7_8") (pintype "input"))
    )
    (net (code "55") (name "/m1-INT") (class "Default")
      (node (ref "R127") (pin "1") (pinfunction "1_1") (pintype "passive"))
      (node (ref "R128") (pin "2") (pinfunction "2_2") (pintype "passive"))
      (node (ref "U13") (pin "5") (pinfunction "A4_5") (pintype "input"))
    )
    (net (code "56") (name "/m1-MISO") (class "Default")
      (node (ref "R121") (pin "1") (pinfunction "1_1") (pintype "passive"))
      (node (ref "R122") (pin "2") (pinfunction "2_2") (pintype "passive"))
      (node (ref "U13") (pin "1") (pinfunction "A1_1") (pintype "input"))
    )
    (net (code "57") (name "/m1-MOSI") (class "Default")
      (node (ref "R123") (pin "1") (pinfunction "1_1") (pintype "passive"))
      (node (ref "R124") (pin "2") (pinfunction "2_2") (pintype "passive"))
      (node (ref "U13") (pin "3") (pinfunction "A2_3") (pintype "input"))
    )
    (net (code "58") (name "/m1-PWM") (class "Default")
      (node (ref "R125") (pin "1") (pinfunction "1_1") (pintype "passive"))
      (node (ref "R126") (pin "2") (pinfunction "2_2") (pintype "passive"))
      (node (ref "U13") (pin "4") (pinfunction "A3_4") (pintype "input"))
    )
    (net (code "59") (name "/m1-RX") (class "Default")
      (node (ref "R129") (pin "1") (pinfunction "1_1") (pintype "passive"))
      (node (ref "R130") (pin "2") (pinfunction "2_2") (pintype "passive"))
      (node (ref "U13") (pin "6") (pinfunction "A5_6") (pintype "input"))
    )
    (net (code "60") (name "/m1-SCK") (class "Default")
      (node (ref "R119") (pin "1") (pinfunction "1_1") (pintype "passive"))
      (node (ref "R120") (pin "2") (pinfunction "2_2") (pintype "passive"))
      (node (ref "U12") (pin "9") (pinfunction "A8_9") (pintype "input"))
    )
    (net (code "61") (name "/m1-SCL") (class "Default")
      (node (ref "R133") (pin "1") (pinfunction "1_1") (pintype "passive"))
      (node (ref "R134") (pin "2") (pinfunction "2_2") (pintype "passive"))
      (node (ref "U13") (pin "8") (pinfunction "A7_8") (pintype "input"))
    )
    (net (code "62") (name "/m1-SDA") (class "Default")
      (node (ref "R135") (pin "1") (pinfunction "1_1") (pintype "passive"))
      (node (ref "R136") (pin "2") (pinfunction "2_2") (pintype "passive"))
      (node (ref "U13") (pin "9") (pinfunction "A8_9") (pintype "input"))
    )
    (net (code "63") (name "/m1-TX") (class "Default")
      (node (ref "R131") (pin "1") (pinfunction "1_1") (pintype "passive"))
      (node (ref "R132") (pin "2") (pinfunction "2_2") (pintype "passive"))
      (node (ref "U13") (pin "7") (pinfunction "A6_7") (pintype "input"))
    )
    (net (code "64") (name "/m1-nRESET") (class "Default")
      (node (ref "R113") (pin "1") (pinfunction "1_1") (pintype "passive"))
      (node (ref "R115") (pin "1") (pinfunction "1_1") (pintype "passive"))
      (node (ref "R116") (pin "2") (pinfunction "2_2") (pintype "passive"))
      (node (ref "U12") (pin "7") (pinfunction "A6_7") (pintype "input"))
    )
    (net (code "65") (name "/m2-INT") (class "Default")
      (node (ref "R105") (pin "1") (pinfunction "1_1") (pintype "passive"))
      (node (ref "R106") (pin "2") (pinfunction "2_2") (pintype "passive"))
      (node (ref "U11") (pin "9") (pinfunction "A8_9") (pintype "input"))
    )
    (net (code "66") (name "/m2-MISO") (class "Default")
      (node (ref "R100") (pin "1") (pinfunction "1_1") (pintype "passive"))
      (node (ref "R101") (pin "2") (pinfunction "2_2") (pintype "passive"))
      (node (ref "U11") (pin "6") (pinfunction "A5_6") (pintype "input"))
    )
    (net (code "67") (name "/m2-PWM") (class "Default")
      (node (ref "R103") (pin "1") (pinfunction "1_1") (pintype "passive"))
      (node (ref "R104") (pin "2") (pinfunction "2_2") (pintype "passive"))
      (node (ref "U11") (pin "8") (pinfunction "A7_8") (pintype "input"))
    )
    (net (code "68") (name "/m2-SCL") (class "Default")
      (node (ref "R109") (pin "1") (pinfunction "1_1") (pintype "passive"))
      (node (ref "R110") (pin "2") (pinfunction "2_2") (pintype "passive"))
      (node (ref "U12") (pin "4") (pinfunction "A3_4") (pintype "input"))
    )
    (net (code "69") (name "/m2-SDA") (class "Default")
      (node (ref "R111") (pin "1") (pinfunction "1_1") (pintype "passive"))
      (node (ref "R112") (pin "2") (pinfunction "2_2") (pintype "passive"))
      (node (ref "U12") (pin "5") (pinfunction "A4_5") (pintype "input"))
    )
    (net (code "70") (name "/m2-nRESET") (class "Default")
      (node (ref "R94") (pin "1") (pinfunction "1_1") (pintype "passive"))
      (node (ref "R96") (pin "1") (pinfunction "1_1") (pintype "passive"))
      (node (ref "R97") (pin "2") (pinfunction "2_2") (pintype "passive"))
      (node (ref "U11") (pin "3") (pinfunction "A2_3") (pintype "input"))
    )
    (net (code "71") (name "/nRESET") (class "Default")
      (node (ref "R115") (pin "2") (pinfunction "2_2") (pintype "passive"))
      (node (ref "R96") (pin "2") (pinfunction "2_2") (pintype "passive"))
    )
    (net (code "81") (name "GND") (class "Default")
      (node (ref "C42") (pin "2") (pinfunction "2_2") (pintype "passive"))
      (node (ref "C43") (pin "2") (pinfunction "2_2") (pintype "passive"))
      (node (ref "C44") (pin "2") (pinfunction "2_2") (pintype "passive"))
      (node (ref "C45") (pin "2") (pinfunction "2_2") (pintype "passive"))
      (node (ref "C46") (pin "2") (pinfunction "2_2") (pintype "passive"))
      (node (ref "C47") (pin "2") (pinfunction "2_2") (pintype "passive"))
      (node (ref "C48") (pin "2") (pinfunction "2_2") (pintype "passive"))
      (node (ref "C49") (pin "1") (pinfunction "1_1") (pintype "passive"))
      (node (ref "C50") (pin "2") (pinfunction "2_2") (pintype "passive"))
      (node (ref "C51") (pin "2") (pinfunction "2_2") (pintype "passive"))
      (node (ref "J17") (pin "8") (pintype "passive"))
      (node (ref "J18") (pin "8") (pintype "passive"))
      (node (ref "J19") (pin "8") (pintype "passive"))
      (node (ref "J20") (pin "8") (pintype "passive"))
      (node (ref "R202") (pin "2") (pinfunction "2_2") (pintype "passive"))
      (node (ref "R203") (pin "2") (pinfunction "2_2") (pintype "passive"))
      (node (ref "R204") (pin "2") (pinfunction "2_2") (pintype "passive"))
      (node (ref "U11") (pin "11") (pinfunction "GND_11") (pintype "power_in"))
      (node (ref "U12") (pin "11") (pinfunction "GND_11") (pintype "power_in"))
      (node (ref "U13") (pin "11") (pinfunction "GND_11") (pintype "power_in"))
    )
    (net (code "82") (name "Net-(U11-OE)") (class "Default")
      (node (ref "R190") (pin "1") (pinfunction "1_1") (pintype "passive"))
      (node (ref "R202") (pin "1") (pinfunction "1_1") (pintype "passive"))
      (node (ref "U11") (pin "10") (pinfunction "OE_10") (pintype "input"))
    )
    (net (code "83") (name "Net-(U12-OE)") (class "Default")
      (node (ref "R191") (pin "1") (pinfunction "1_1") (pintype "passive"))
      (node (ref "R203") (pin "1") (pinfunction "1_1") (pintype "passive"))
      (node (ref "U12") (pin "10") (pinfunction "OE_10") (pintype "input"))
    )
    (net (code "84") (name "Net-(U13-OE)") (class "Default")
      (node (ref "R192") (pin "1") (pinfunction "1_1") (pintype "passive"))
      (node (ref "R204") (pin "1") (pinfunction "1_1") (pintype "passive"))
      (node (ref "U13") (pin "10") (pinfunction "OE_10") (pintype "input"))
    )
    (net (code "85") (name "VDDIO_Periph") (class "Default")
      (node (ref "C45") (pin "1") (pinfunction "1_1") (pintype "passive"))
      (node (ref "C46") (pin "1") (pinfunction "1_1") (pintype "passive"))
      (node (ref "C47") (pin "1") (pinfunction "1_1") (pintype "passive"))
      (node (ref "R190") (pin "2") (pinfunction "2_2") (pintype "passive"))
      (node (ref "R191") (pin "2") (pinfunction "2_2") (pintype "passive"))
      (node (ref "R192") (pin "2") (pinfunction "2_2") (pintype "passive"))
      (node (ref "U11") (pin "2") (pinfunction "VCCA_2") (pintype "power_in"))
      (node (ref "U12") (pin "2") (pinfunction "VCCA_2") (pintype "power_in"))
      (node (ref "U13") (pin "2") (pinfunction "VCCA_2") (pintype "power_in"))
    )
  )
)
